# USB2CAN.net
KiCad netlist of a schematic drawn in Altium Designer
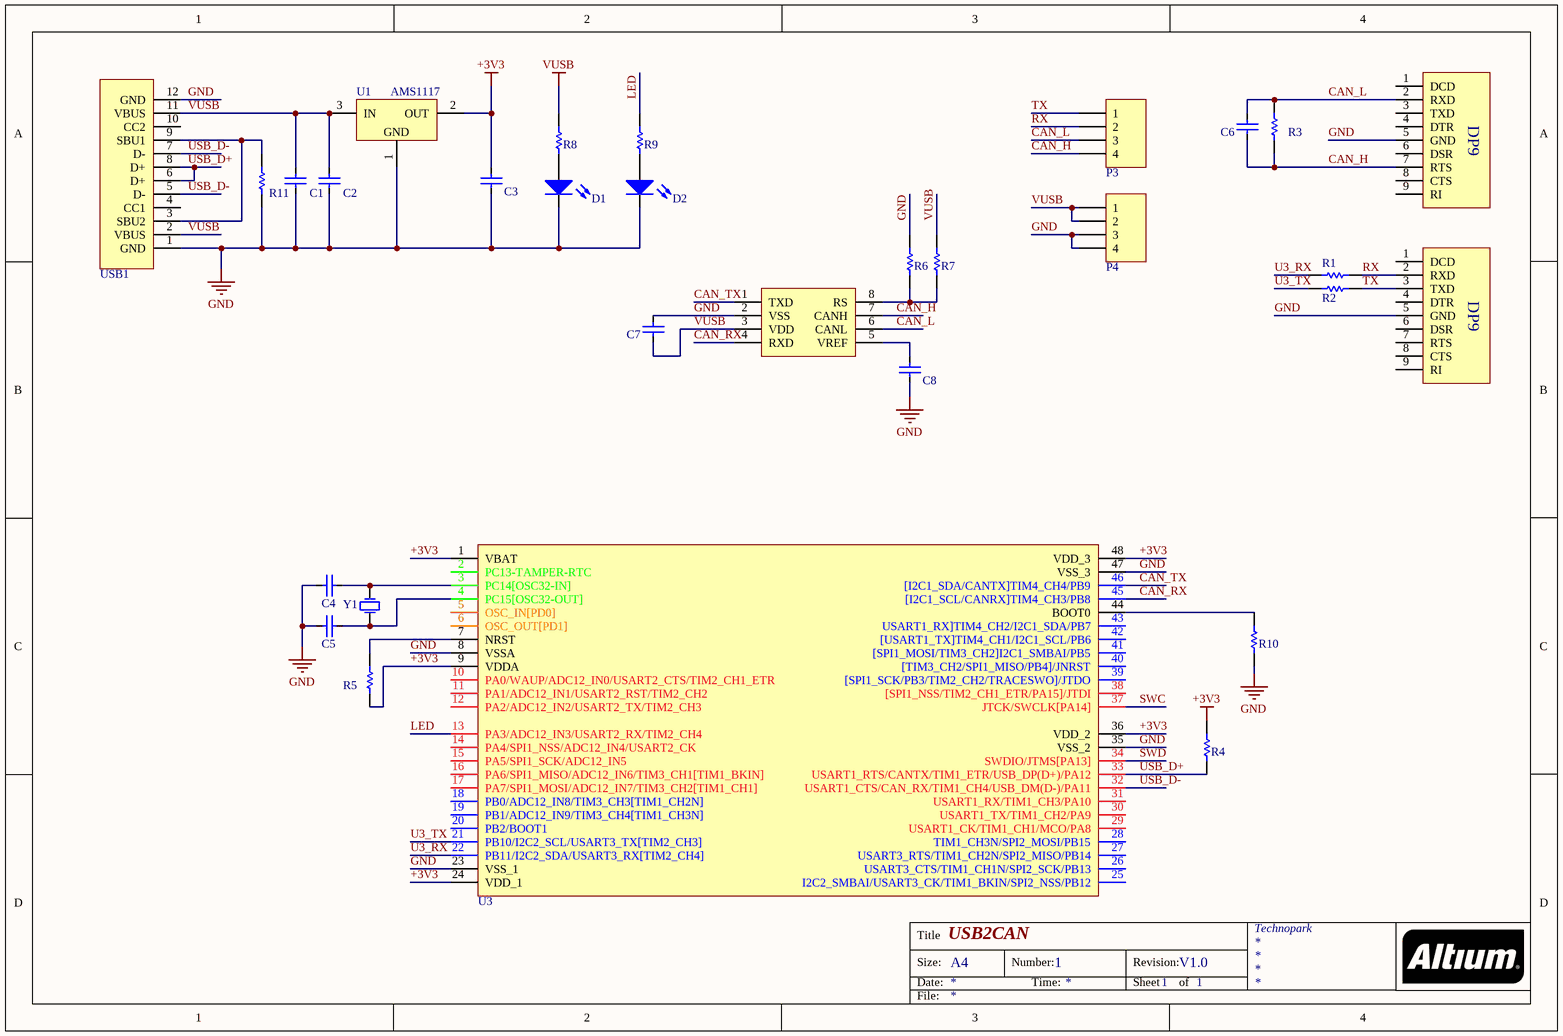
[diagram p0: USB2CAN.SchDoc]

(export (version "E")
  (design (tool "Eeschema 10.0.6"))
  (components
    (comp (ref "C1") (value "CAP_NP") (footprint "C_0805") (libsource (lib "ThanhTung") (part "CAP_NP")))
    (comp (ref "C2") (value "CAP_NP") (footprint "C_0805") (libsource (lib "ThanhTung") (part "CAP_NP")))
    (comp (ref "C3") (value "CAP_NP") (footprint "C_0805") (libsource (lib "ThanhTung") (part "CAP_NP")))
    (comp (ref "C4") (value "CAP_NP") (footprint "C_0603") (libsource (lib "ThanhTung") (part "CAP_NP")))
    (comp (ref "C5") (value "CAP_NP") (footprint "C_0603") (libsource (lib "ThanhTung") (part "CAP_NP")))
    (comp (ref "C6") (value "CAP_NP") (footprint "C_0603") (libsource (lib "ThanhTung") (part "CAP_NP")))
    (comp (ref "C7") (value "CAP_NP") (footprint "C_0603") (libsource (lib "ThanhTung") (part "CAP_NP")))
    (comp (ref "C8") (value "CAP_NP") (footprint "C_0603") (libsource (lib "ThanhTung") (part "CAP_NP")))
    (comp (ref "D1")
      (value "LED")
      (footprint "LED-0603-R")
      (description "Blue 465nm LED Indication - Discrete 3.8V 0603 (1608 Metric)")
      (fields
        (field (name "MANUFACTURER") "Everlight Electronics Co Ltd")
        (field (name "MANUFACTURER PART NUMBER") "QTLP600CBTR")
      )
      (libsource (lib "ThanhTung") (part "LED"))
    )
    (comp (ref "D2")
      (value "LED")
      (footprint "LED-0603-G")
      (description "Blue 465nm LED Indication - Discrete 3.8V 0603 (1608 Metric)")
      (fields
        (field (name "MANUFACTURER") "Everlight Electronics Co Ltd")
        (field (name "MANUFACTURER PART NUMBER") "QTLP600CBTR")
      )
      (libsource (lib "ThanhTung") (part "LED"))
    )
    (comp (ref "P1") (value "DP9") (footprint "DR9T MALE") (libsource (lib "ThanhTung") (part "DP9")))
    (comp (ref "P2") (value "DP9") (footprint "DR9T MALE") (libsource (lib "ThanhTung") (part "DP9")))
    (comp (ref "P3") (value "HEADER 4") (footprint "JUMP 4") (libsource (lib "ThanhTung") (part "HEADER 4")))
    (comp (ref "P4") (value "HEADER 4") (footprint "JUMP 4") (libsource (lib "ThanhTung") (part "HEADER 4")))
    (comp (ref "R1") (value "R") (footprint "R_0603") (libsource (lib "ThanhTung") (part "RESISTOR")))
    (comp (ref "R2") (value "R") (footprint "R_0603") (libsource (lib "ThanhTung") (part "RESISTOR")))
    (comp (ref "R3") (value "R") (footprint "R_0603") (libsource (lib "ThanhTung") (part "RESISTOR")))
    (comp (ref "R4") (value "R") (footprint "R_0603") (libsource (lib "ThanhTung") (part "RESISTOR")))
    (comp (ref "R5") (value "R") (footprint "R_0603") (libsource (lib "ThanhTung") (part "RESISTOR")))
    (comp (ref "R6") (value "R") (footprint "R_0603") (libsource (lib "ThanhTung") (part "RESISTOR")))
    (comp (ref "R7") (value "R") (footprint "R_0603") (libsource (lib "ThanhTung") (part "RESISTOR")))
    (comp (ref "R8") (value "R") (footprint "R_0603") (libsource (lib "ThanhTung") (part "RESISTOR")))
    (comp (ref "R9") (value "R") (footprint "R_0603") (libsource (lib "ThanhTung") (part "RESISTOR")))
    (comp (ref "R10") (value "R") (footprint "R_0603") (libsource (lib "ThanhTung") (part "RESISTOR")))
    (comp (ref "R11") (value "R") (footprint "R_0603") (libsource (lib "ThanhTung") (part "RESISTOR")))
    (comp (ref "U1") (value "AMS1117") (footprint "SOT 89") (libsource (lib "ThanhTung") (part "AMS1117")))
    (comp (ref "U2")
      (value "CAN TRANSEIVER")
      (footprint "SOP8")
      (libsource (lib "ThanhTung") (part "MCP2551"))
    )
    (comp (ref "U3")
      (value "STM32F103C8T6")
      (footprint "LQFP-48")
      (fields (field (name "MANUFACTURER") "STMicroelectronics"))
      (libsource (lib "ThanhTung") (part "STM32F103C8T6"))
    )
    (comp (ref "USB1")
      (value "USB C 16P")
      (footprint "USB C 16P")
      (libsource (lib "ThanhTung") (part "USB C 16P"))
    )
    (comp (ref "Y1")
      (value "12MHz")
      (footprint "CRYSTAL-3225")
      (libsource (lib "ThanhTung") (part "CRYSTAL-3225"))
    )
  )
  (nets
    (net (code "1") (name "+3V3") (class "Default")
      (node (ref "C3") (pin "2") (pinfunction "2_2") (pintype "passive"))
      (node (ref "R4") (pin "2") (pinfunction "2_2") (pintype "passive"))
      (node (ref "R5") (pin "1") (pinfunction "1_1") (pintype "passive"))
      (node (ref "U1") (pin "2") (pinfunction "OUT_2") (pintype "passive"))
      (node (ref "U3") (pin "1") (pinfunction "VBAT_1") (pintype "power_in"))
      (node (ref "U3") (pin "24") (pinfunction "VDD_1_24") (pintype "power_in"))
      (node (ref "U3") (pin "36") (pinfunction "VDD_2_36") (pintype "power_in"))
      (node (ref "U3") (pin "48") (pinfunction "VDD_3_48") (pintype "power_in"))
      (node (ref "U3") (pin "9") (pinfunction "VDDA_9") (pintype "power_in"))
    )
    (net (code "2") (name "/CAN_H") (class "Default")
      (node (ref "C6") (pin "2") (pinfunction "2_2") (pintype "passive"))
      (node (ref "P1") (pin "7") (pinfunction "RTS_7") (pintype "passive"))
      (node (ref "P3") (pin "4") (pinfunction "4_4") (pintype "passive"))
      (node (ref "R3") (pin "1") (pinfunction "1_1") (pintype "passive"))
      (node (ref "U2") (pin "7") (pinfunction "CANH_7") (pintype "passive"))
    )
    (net (code "3") (name "/CAN_L") (class "Default")
      (node (ref "C6") (pin "1") (pinfunction "1_1") (pintype "passive"))
      (node (ref "P1") (pin "2") (pinfunction "RXD_2") (pintype "passive"))
      (node (ref "P3") (pin "3") (pinfunction "3_3") (pintype "passive"))
      (node (ref "R3") (pin "2") (pinfunction "2_2") (pintype "passive"))
      (node (ref "U2") (pin "6") (pinfunction "CANL_6") (pintype "passive"))
    )
    (net (code "4") (name "/CAN_RX") (class "Default")
      (node (ref "U2") (pin "4") (pinfunction "RXD_4") (pintype "passive"))
      (node (ref "U3") (pin "45") (pinfunction "[I2C1_SCL/CANRX]TIM4_CH3/PB8_45") (pintype "power_in"))
    )
    (net (code "5") (name "/CAN_TX") (class "Default")
      (node (ref "U2") (pin "1") (pinfunction "TXD_1") (pintype "passive"))
      (node (ref "U3") (pin "46") (pinfunction "[I2C1_SDA/CANTX]TIM4_CH4/PB9_46") (pintype "power_in"))
    )
    (net (code "6") (name "/LED") (class "Default")
      (node (ref "R9") (pin "1") (pinfunction "1_1") (pintype "passive"))
      (node (ref "U3") (pin "13") (pinfunction "PA3/ADC12_IN3/USART2_RX/TIM2_CH4_13") (pintype "power_in"))
    )
    (net (code "7") (name "/RX") (class "Default")
      (node (ref "P2") (pin "2") (pinfunction "RXD_2") (pintype "passive"))
      (node (ref "P3") (pin "2") (pinfunction "2_2") (pintype "passive"))
      (node (ref "R1") (pin "2") (pinfunction "2_2") (pintype "passive"))
    )
    (net (code "8") (name "/SWC") (class "Default")
      (node (ref "U3") (pin "37") (pinfunction "JTCK/SWCLK[PA14]_37") (pintype "power_in"))
    )
    (net (code "9") (name "/SWD") (class "Default")
      (node (ref "U3") (pin "34") (pinfunction "SWDIO/JTMS[PA13]_34") (pintype "power_in"))
    )
    (net (code "10") (name "/TX") (class "Default")
      (node (ref "P2") (pin "3") (pinfunction "TXD_3") (pintype "passive"))
      (node (ref "P3") (pin "1") (pinfunction "1_1") (pintype "passive"))
      (node (ref "R2") (pin "2") (pinfunction "2_2") (pintype "passive"))
    )
    (net (code "11") (name "/U3_RX") (class "Default")
      (node (ref "R1") (pin "1") (pinfunction "1_1") (pintype "passive"))
      (node (ref "U3") (pin "22") (pinfunction "PB11/I2C2_SDA/USART3_RX[TIM2_CH4]_22") (pintype "power_in"))
    )
    (net (code "12") (name "/U3_TX") (class "Default")
      (node (ref "R2") (pin "1") (pinfunction "1_1") (pintype "passive"))
      (node (ref "U3") (pin "21") (pinfunction "PB10/I2C2_SCL/USART3_TX[TIM2_CH3]_21") (pintype "power_in"))
    )
    (net (code "13") (name "/USB_D+") (class "Default")
      (node (ref "R4") (pin "1") (pinfunction "1_1") (pintype "passive"))
      (node (ref "U3") (pin "33") (pinfunction "USART1_RTS/CANTX/TIM1_ETR/USB_DP(D+)/PA12_33") (pintype "power_in"))
      (node (ref "USB1") (pin "6") (pinfunction "D+_6") (pintype "passive"))
      (node (ref "USB1") (pin "8") (pinfunction "D+_8") (pintype "passive"))
    )
    (net (code "14") (name "/USB_D-") (class "Default")
      (node (ref "U3") (pin "32") (pinfunction "USART1_CTS/CAN_RX/TIM1_CH4/USB_DM(D-)/PA11_32") (pintype "power_in"))
      (node (ref "USB1") (pin "5") (pinfunction "D-_5") (pintype "passive"))
      (node (ref "USB1") (pin "7") (pinfunction "D-_7") (pintype "passive"))
    )
    (net (code "15") (name "GND") (class "Default")
      (node (ref "C1") (pin "1") (pinfunction "1_1") (pintype "passive"))
      (node (ref "C2") (pin "1") (pinfunction "1_1") (pintype "passive"))
      (node (ref "C3") (pin "1") (pinfunction "1_1") (pintype "passive"))
      (node (ref "C4") (pin "2") (pinfunction "2_2") (pintype "passive"))
      (node (ref "C5") (pin "2") (pinfunction "2_2") (pintype "passive"))
      (node (ref "C7") (pin "1") (pinfunction "1_1") (pintype "passive"))
      (node (ref "C8") (pin "2") (pinfunction "2_2") (pintype "passive"))
      (node (ref "D1") (pin "2") (pinfunction "K_2") (pintype "passive"))
      (node (ref "D2") (pin "2") (pinfunction "K_2") (pintype "passive"))
      (node (ref "P1") (pin "5") (pinfunction "GND_5") (pintype "passive"))
      (node (ref "P2") (pin "5") (pinfunction "GND_5") (pintype "passive"))
      (node (ref "P4") (pin "3") (pinfunction "3_3") (pintype "passive"))
      (node (ref "P4") (pin "4") (pinfunction "4_4") (pintype "passive"))
      (node (ref "R10") (pin "1") (pinfunction "1_1") (pintype "passive"))
      (node (ref "R11") (pin "2") (pinfunction "2_2") (pintype "passive"))
      (node (ref "R6") (pin "1") (pinfunction "1_1") (pintype "passive"))
      (node (ref "U1") (pin "1") (pinfunction "GND_1") (pintype "passive"))
      (node (ref "U2") (pin "2") (pinfunction "VSS_2") (pintype "passive"))
      (node (ref "U3") (pin "23") (pinfunction "VSS_1_23") (pintype "power_in"))
      (node (ref "U3") (pin "35") (pinfunction "VSS_2_35") (pintype "power_in"))
      (node (ref "U3") (pin "47") (pinfunction "VSS_3_47") (pintype "power_in"))
      (node (ref "U3") (pin "8") (pinfunction "VSSA_8") (pintype "power_in"))
      (node (ref "USB1") (pin "1") (pinfunction "GND_1") (pintype "passive"))
      (node (ref "USB1") (pin "12") (pinfunction "GND_12") (pintype "passive"))
    )
    (net (code "16") (name "Net-(D1-A)") (class "Default")
      (node (ref "D1") (pin "1") (pinfunction "A_1") (pintype "passive"))
      (node (ref "R8") (pin "2") (pinfunction "2_2") (pintype "passive"))
    )
    (net (code "17") (name "Net-(D2-A)") (class "Default")
      (node (ref "D2") (pin "1") (pinfunction "A_1") (pintype "passive"))
      (node (ref "R9") (pin "2") (pinfunction "2_2") (pintype "passive"))
    )
    (net (code "18") (name "Net-(U2-RS)") (class "Default")
      (node (ref "R6") (pin "2") (pinfunction "2_2") (pintype "passive"))
      (node (ref "R7") (pin "1") (pinfunction "1_1") (pintype "passive"))
      (node (ref "U2") (pin "8") (pinfunction "RS_8") (pintype "passive"))
    )
    (net (code "19") (name "Net-(U2-VREF)") (class "Default")
      (node (ref "C8") (pin "1") (pinfunction "1_1") (pintype "passive"))
      (node (ref "U2") (pin "5") (pinfunction "VREF_5") (pintype "passive"))
    )
    (net (code "20") (name "Net-(U3-BOOT0)") (class "Default")
      (node (ref "R10") (pin "2") (pinfunction "2_2") (pintype "passive"))
      (node (ref "U3") (pin "44") (pinfunction "BOOT0_44") (pintype "power_in"))
    )
    (net (code "21") (name "Net-(U3-NRST)") (class "Default")
      (node (ref "R5") (pin "2") (pinfunction "2_2") (pintype "passive"))
      (node (ref "U3") (pin "7") (pinfunction "NRST_7") (pintype "power_in"))
    )
    (net (code "22") (name "Net-(U3-PC14[OSC32-IN])") (class "Default")
      (node (ref "C4") (pin "1") (pinfunction "1_1") (pintype "passive"))
      (node (ref "U3") (pin "3") (pinfunction "PC14[OSC32-IN]_3") (pintype "power_in"))
      (node (ref "Y1") (pin "3") (pinfunction "OSC2_3") (pintype "passive"))
    )
    (net (code "23") (name "Net-(U3-PC15[OSC32-OUT])") (class "Default")
      (node (ref "C5") (pin "1") (pinfunction "1_1") (pintype "passive"))
      (node (ref "U3") (pin "4") (pinfunction "PC15[OSC32-OUT]_4") (pintype "power_in"))
      (node (ref "Y1") (pin "1") (pinfunction "OSC1_1") (pintype "passive"))
    )
    (net (code "24") (name "Net-(USB1-SBU1)") (class "Default")
      (node (ref "R11") (pin "1") (pinfunction "1_1") (pintype "passive"))
      (node (ref "USB1") (pin "3") (pinfunction "SBU2_3") (pintype "passive"))
      (node (ref "USB1") (pin "9") (pinfunction "SBU1_9") (pintype "passive"))
    )
    (net (code "25") (name "VUSB") (class "Default")
      (node (ref "C1") (pin "2") (pinfunction "2_2") (pintype "passive"))
      (node (ref "C2") (pin "2") (pinfunction "2_2") (pintype "passive"))
      (node (ref "C7") (pin "2") (pinfunction "2_2") (pintype "passive"))
      (node (ref "P4") (pin "1") (pinfunction "1_1") (pintype "passive"))
      (node (ref "P4") (pin "2") (pinfunction "2_2") (pintype "passive"))
      (node (ref "R7") (pin "2") (pinfunction "2_2") (pintype "passive"))
      (node (ref "R8") (pin "1") (pinfunction "1_1") (pintype "passive"))
      (node (ref "U1") (pin "3") (pinfunction "IN_3") (pintype "passive"))
      (node (ref "U2") (pin "3") (pinfunction "VDD_3") (pintype "passive"))
      (node (ref "USB1") (pin "11") (pinfunction "VBUS_11") (pintype "passive"))
      (node (ref "USB1") (pin "2") (pinfunction "VBUS_2") (pintype "passive"))
    )
    (net (code "26") (name "unconnected-(P1-CTS-Pad8)") (class "Default")
      (node (ref "P1") (pin "8") (pinfunction "CTS_8") (pintype "passive"))
    )
    (net (code "27") (name "unconnected-(P1-DCD-Pad1)") (class "Default")
      (node (ref "P1") (pin "1") (pinfunction "DCD_1") (pintype "passive"))
    )
    (net (code "28") (name "unconnected-(P1-DSR-Pad6)") (class "Default")
      (node (ref "P1") (pin "6") (pinfunction "DSR_6") (pintype "passive"))
    )
    (net (code "29") (name "unconnected-(P1-DTR-Pad4)") (class "Default")
      (node (ref "P1") (pin "4") (pinfunction "DTR_4") (pintype "passive"))
    )
    (net (code "30") (name "unconnected-(P1-RI-Pad9)") (class "Default")
      (node (ref "P1") (pin "9") (pinfunction "RI_9") (pintype "passive"))
    )
    (net (code "31") (name "unconnected-(P1-TXD-Pad3)") (class "Default")
      (node (ref "P1") (pin "3") (pinfunction "TXD_3") (pintype "passive"))
    )
    (net (code "32") (name "unconnected-(P2-CTS-Pad8)") (class "Default")
      (node (ref "P2") (pin "8") (pinfunction "CTS_8") (pintype "passive"))
    )
    (net (code "33") (name "unconnected-(P2-DCD-Pad1)") (class "Default")
      (node (ref "P2") (pin "1") (pinfunction "DCD_1") (pintype "passive"))
    )
    (net (code "34") (name "unconnected-(P2-DSR-Pad6)") (class "Default")
      (node (ref "P2") (pin "6") (pinfunction "DSR_6") (pintype "passive"))
    )
    (net (code "35") (name "unconnected-(P2-DTR-Pad4)") (class "Default")
      (node (ref "P2") (pin "4") (pinfunction "DTR_4") (pintype "passive"))
    )
    (net (code "36") (name "unconnected-(P2-RI-Pad9)") (class "Default")
      (node (ref "P2") (pin "9") (pinfunction "RI_9") (pintype "passive"))
    )
    (net (code "37") (name "unconnected-(P2-RTS-Pad7)") (class "Default")
      (node (ref "P2") (pin "7") (pinfunction "RTS_7") (pintype "passive"))
    )
    (net (code "38") (name "unconnected-(U3-I2C2_SMBAI{slash}USART3_CK{slash}TIM1_BKIN{slash}SPI2_NSS{slash}PB12-Pad25)") (class "Default")
      (node (ref "U3") (pin "25") (pinfunction "I2C2_SMBAI/USART3_CK/TIM1_BKIN/SPI2_NSS/PB12_25") (pintype "power_in"))
    )
    (net (code "39") (name "unconnected-(U3-OSC_IN[PD0]-Pad5)") (class "Default")
      (node (ref "U3") (pin "5") (pinfunction "OSC_IN[PD0]_5") (pintype "power_in"))
    )
    (net (code "40") (name "unconnected-(U3-OSC_OUT[PD1]-Pad6)") (class "Default")
      (node (ref "U3") (pin "6") (pinfunction "OSC_OUT[PD1]_6") (pintype "power_in"))
    )
    (net (code "41") (name "unconnected-(U3-PA0{slash}WAUP{slash}ADC12_IN0{slash}USART2_CTS{slash}TIM2_CH1_ETR-Pad10)") (class "Default")
      (node (ref "U3") (pin "10") (pinfunction "PA0/WAUP/ADC12_IN0/USART2_CTS/TIM2_CH1_ETR_10") (pintype "power_in"))
    )
    (net (code "42") (name "unconnected-(U3-PA1{slash}ADC12_IN1{slash}USART2_RST{slash}TIM2_CH2-Pad11)") (class "Default")
      (node (ref "U3") (pin "11") (pinfunction "PA1/ADC12_IN1/USART2_RST/TIM2_CH2_11") (pintype "power_in"))
    )
    (net (code "43") (name "unconnected-(U3-PA2{slash}ADC12_IN2{slash}USART2_TX{slash}TIM2_CH3-Pad12)") (class "Default")
      (node (ref "U3") (pin "12") (pinfunction "PA2/ADC12_IN2/USART2_TX/TIM2_CH3_12") (pintype "power_in"))
    )
    (net (code "44") (name "unconnected-(U3-PA4{slash}SPI1_NSS{slash}ADC12_IN4{slash}USART2_CK-Pad14)") (class "Default")
      (node (ref "U3") (pin "14") (pinfunction "PA4/SPI1_NSS/ADC12_IN4/USART2_CK_14") (pintype "power_in"))
    )
    (net (code "45") (name "unconnected-(U3-PA5{slash}SPI1_SCK{slash}ADC12_IN5-Pad15)") (class "Default")
      (node (ref "U3") (pin "15") (pinfunction "PA5/SPI1_SCK/ADC12_IN5_15") (pintype "power_in"))
    )
    (net (code "46") (name "unconnected-(U3-PA6{slash}SPI1_MISO{slash}ADC12_IN6{slash}TIM3_CH1[TIM1_BKIN]-Pad16)") (class "Default")
      (node (ref "U3") (pin "16") (pinfunction "PA6/SPI1_MISO/ADC12_IN6/TIM3_CH1[TIM1_BKIN]_16") (pintype "power_in"))
    )
    (net (code "47") (name "unconnected-(U3-PA7{slash}SPI1_MOSI{slash}ADC12_IN7{slash}TIM3_CH2[TIM1_CH1]-Pad17)") (class "Default")
      (node (ref "U3") (pin "17") (pinfunction "PA7/SPI1_MOSI/ADC12_IN7/TIM3_CH2[TIM1_CH1]_17") (pintype "power_in"))
    )
    (net (code "48") (name "unconnected-(U3-PB0{slash}ADC12_IN8{slash}TIM3_CH3[TIM1_CH2N]-Pad18)") (class "Default")
      (node (ref "U3") (pin "18") (pinfunction "PB0/ADC12_IN8/TIM3_CH3[TIM1_CH2N]_18") (pintype "power_in"))
    )
    (net (code "49") (name "unconnected-(U3-PB1{slash}ADC12_IN9{slash}TIM3_CH4[TIM1_CH3N]-Pad19)") (class "Default")
      (node (ref "U3") (pin "19") (pinfunction "PB1/ADC12_IN9/TIM3_CH4[TIM1_CH3N]_19") (pintype "power_in"))
    )
    (net (code "50") (name "unconnected-(U3-PB2{slash}BOOT1-Pad20)") (class "Default")
      (node (ref "U3") (pin "20") (pinfunction "PB2/BOOT1_20") (pintype "power_in"))
    )
    (net (code "51") (name "unconnected-(U3-PC13-TAMPER-RTC-Pad2)") (class "Default")
      (node (ref "U3") (pin "2") (pinfunction "PC13-TAMPER-RTC_2") (pintype "power_in"))
    )
    (net (code "52") (name "unconnected-(U3-TIM1_CH3N{slash}SPI2_MOSI{slash}PB15-Pad28)") (class "Default")
      (node (ref "U3") (pin "28") (pinfunction "TIM1_CH3N/SPI2_MOSI/PB15_28") (pintype "power_in"))
    )
    (net (code "53") (name "unconnected-(U3-USART1_CK{slash}TIM1_CH1{slash}MCO{slash}PA8-Pad29)") (class "Default")
      (node (ref "U3") (pin "29") (pinfunction "USART1_CK/TIM1_CH1/MCO/PA8_29") (pintype "power_in"))
    )
    (net (code "54") (name "unconnected-(U3-USART1_RX]TIM4_CH2{slash}I2C1_SDA{slash}PB7-Pad43)") (class "Default")
      (node (ref "U3") (pin "43") (pinfunction "USART1_RX]TIM4_CH2/I2C1_SDA/PB7_43") (pintype "power_in"))
    )
    (net (code "55") (name "unconnected-(U3-USART1_RX{slash}TIM1_CH3{slash}PA10-Pad31)") (class "Default")
      (node (ref "U3") (pin "31") (pinfunction "USART1_RX/TIM1_CH3/PA10_31") (pintype "power_in"))
    )
    (net (code "56") (name "unconnected-(U3-USART1_TX{slash}TIM1_CH2{slash}PA9-Pad30)") (class "Default")
      (node (ref "U3") (pin "30") (pinfunction "USART1_TX/TIM1_CH2/PA9_30") (pintype "power_in"))
    )
    (net (code "57") (name "unconnected-(U3-USART3_CTS{slash}TIM1_CH1N{slash}SPI2_SCK{slash}PB13-Pad26)") (class "Default")
      (node (ref "U3") (pin "26") (pinfunction "USART3_CTS/TIM1_CH1N/SPI2_SCK/PB13_26") (pintype "power_in"))
    )
    (net (code "58") (name "unconnected-(U3-USART3_RTS{slash}TIM1_CH2N{slash}SPI2_MISO{slash}PB14-Pad27)") (class "Default")
      (node (ref "U3") (pin "27") (pinfunction "USART3_RTS/TIM1_CH2N/SPI2_MISO/PB14_27") (pintype "power_in"))
    )
    (net (code "59") (name "unconnected-(U3-[SPI1_MOSI{slash}TIM3_CH2]I2C1_SMBAI{slash}PB5-Pad41)") (class "Default")
      (node (ref "U3") (pin "41") (pinfunction "[SPI1_MOSI/TIM3_CH2]I2C1_SMBAI/PB5_41") (pintype "power_in"))
    )
    (net (code "60") (name "unconnected-(U3-[SPI1_NSS{slash}TIM2_CH1_ETR{slash}PA15]{slash}JTDI-Pad38)") (class "Default")
      (node (ref "U3") (pin "38") (pinfunction "[SPI1_NSS/TIM2_CH1_ETR/PA15]/JTDI_38") (pintype "power_in"))
    )
    (net (code "61") (name "unconnected-(U3-[SPI1_SCK{slash}PB3{slash}TIM2_CH2{slash}TRACESWO]{slash}JTDO-Pad39)") (class "Default")
      (node (ref "U3") (pin "39") (pinfunction "[SPI1_SCK/PB3/TIM2_CH2/TRACESWO]/JTDO_39") (pintype "power_in"))
    )
    (net (code "62") (name "unconnected-(U3-[TIM3_CH2{slash}SPI1_MISO{slash}PB4]{slash}JNRST-Pad40)") (class "Default")
      (node (ref "U3") (pin "40") (pinfunction "[TIM3_CH2/SPI1_MISO/PB4]/JNRST_40") (pintype "power_in"))
    )
    (net (code "63") (name "unconnected-(U3-[USART1_TX]TIM4_CH1{slash}I2C1_SCL{slash}PB6-Pad42)") (class "Default")
      (node (ref "U3") (pin "42") (pinfunction "[USART1_TX]TIM4_CH1/I2C1_SCL/PB6_42") (pintype "power_in"))
    )
    (net (code "64") (name "unconnected-(USB1-CC1-Pad4)") (class "Default")
      (node (ref "USB1") (pin "4") (pinfunction "CC1_4") (pintype "passive"))
    )
    (net (code "65") (name "unconnected-(USB1-CC2-Pad10)") (class "Default")
      (node (ref "USB1") (pin "10") (pinfunction "CC2_10") (pintype "passive"))
    )
    (net (code "66") (name "unconnected-(Y1-OSC3-Pad2)") (class "Default")
      (node (ref "Y1") (pin "2") (pinfunction "OSC3_2") (pintype "passive"))
    )
    (net (code "67") (name "unconnected-(Y1-OSC4-Pad4)") (class "Default")
      (node (ref "Y1") (pin "4") (pinfunction "OSC4_4") (pintype "passive"))
    )
  )
)
